# cs301_template.net
KiCad netlist of a schematic drawn in Altium Designer
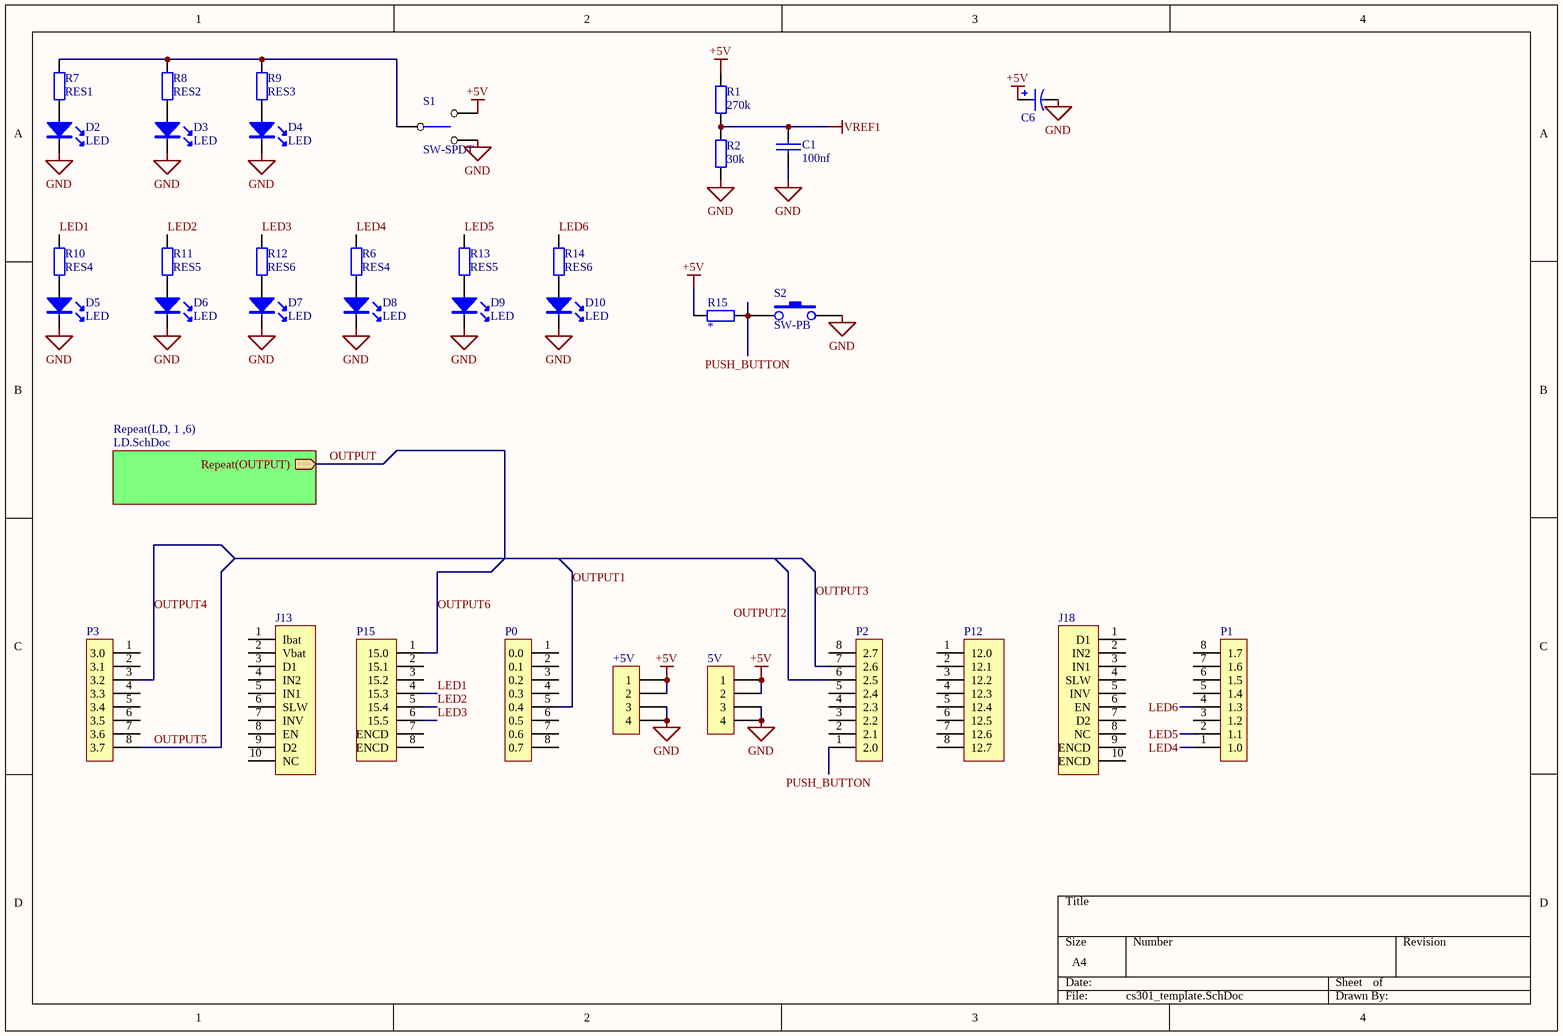
[diagram p0: cs301_template.SchDoc]

(export (version "E")
  (design (tool "Eeschema 10.0.6"))
  (components
    (comp (ref "+5V")
      (value "5V")
      (footprint "IDC4")
      (description "Connector")
      (libsource (lib "Miscellaneous Devices") (part "CON4"))
    )
    (comp (ref "5V")
      (value "5V")
      (footprint "IDC4")
      (description "Connector")
      (libsource (lib "Miscellaneous Devices") (part "CON4"))
    )
    (comp (ref "C1")
      (value "100nf")
      (footprint "0805 CAP")
      (description "SMT ceramic capacitor 0805 size")
      (libsource (lib "COMSYS301_2025") (part "CerCap_SMT_0805"))
    )
    (comp (ref "C6")
      (value "*")
      (footprint "CAP POL 8x5.4mm SMT")
      (description "CAP ALUM 22UF 20% 50V SMD (Model: UWX1H220MCL1GB)")
      (fields
        (field (name "MANUFACTURER") "Nichicon")
        (field (name "MANUFACTURER PART NUMBER") "UWX1V220MCL1GB")
      )
      (libsource (lib "COMSYS301_2025") (part "ElecCap_SMT_8D0"))
    )
    (comp (ref "D2") (value "LED") (footprint "LED0.1/5MM") (libsource (lib "COMSYS301_2025") (part "LED")))
    (comp (ref "D3") (value "LED") (footprint "LED0.1/5MM") (libsource (lib "COMSYS301_2025") (part "LED")))
    (comp (ref "D4") (value "LED") (footprint "LED0.1/5MM") (libsource (lib "COMSYS301_2025") (part "LED")))
    (comp (ref "D5") (value "LED") (footprint "LED0.1/5MM") (libsource (lib "COMSYS301_2025") (part "LED")))
    (comp (ref "D6") (value "LED") (footprint "LED0.1/5MM") (libsource (lib "COMSYS301_2025") (part "LED")))
    (comp (ref "D7") (value "LED") (footprint "LED0.1/5MM") (libsource (lib "COMSYS301_2025") (part "LED")))
    (comp (ref "D8") (value "LED") (footprint "LED0.1/5MM") (libsource (lib "COMSYS301_2025") (part "LED")))
    (comp (ref "D9") (value "LED") (footprint "LED0.1/5MM") (libsource (lib "COMSYS301_2025") (part "LED")))
    (comp (ref "D10") (value "LED") (footprint "LED0.1/5MM") (libsource (lib "COMSYS301_2025") (part "LED")))
    (comp (ref "J13")
      (value "CON10")
      (footprint "idc10")
      (description "Connector")
      (libsource (lib "Miscellaneous Devices") (part "CON10"))
    )
    (comp (ref "J18")
      (value "CON10")
      (footprint "IDC10")
      (description "Connector")
      (libsource (lib "") (part "CON10_1"))
    )
    (comp (ref "P0")
      (value "P0")
      (footprint "idc8")
      (description "Connector")
      (libsource (lib "") (part "CON8_1"))
    )
    (comp (ref "P1")
      (value "P1")
      (footprint "idc8")
      (description "Connector")
      (libsource (lib "") (part "CON8_2"))
    )
    (comp (ref "P2")
      (value "P2")
      (footprint "idc8")
      (description "Connector")
      (libsource (lib "") (part "CON8_2"))
    )
    (comp (ref "P3")
      (value "P3")
      (footprint "idc8")
      (description "Connector")
      (libsource (lib "Miscellaneous Devices") (part "CON8"))
    )
    (comp (ref "P12")
      (value "P12")
      (footprint "idc8")
      (description "Connector")
      (libsource (lib "Miscellaneous Devices") (part "CON8_1"))
    )
    (comp (ref "P15")
      (value "P15")
      (footprint "idc8")
      (description "Connector")
      (libsource (lib "") (part "CON8_1_1"))
    )
    (comp (ref "R1")
      (value "270k")
      (footprint "0805 RES")
      (description "0805 resistor")
      (fields (field (name "PUBLISHER") "Altium Limited"))
      (libsource (lib "COMSYS301_2025") (part "Res_SMT_0805"))
    )
    (comp (ref "R2")
      (value "30k")
      (footprint "0805 RES")
      (description "0805 resistor")
      (fields (field (name "PUBLISHER") "Altium Limited"))
      (libsource (lib "COMSYS301_2025") (part "Res_SMT_0805"))
    )
    (comp (ref "R6")
      (value "RES4")
      (footprint "0805 RES")
      (description "0805 resistor")
      (fields (field (name "PUBLISHER") "Altium Limited"))
      (libsource (lib "COMSYS301_2025") (part "Res_SMT_0805"))
    )
    (comp (ref "R7")
      (value "RES1")
      (footprint "0805 RES")
      (description "0805 resistor")
      (fields (field (name "PUBLISHER") "Altium Limited"))
      (libsource (lib "COMSYS301_2025") (part "Res_SMT_0805"))
    )
    (comp (ref "R8")
      (value "RES2")
      (footprint "0805 RES")
      (description "0805 resistor")
      (fields (field (name "PUBLISHER") "Altium Limited"))
      (libsource (lib "COMSYS301_2025") (part "Res_SMT_0805"))
    )
    (comp (ref "R9")
      (value "RES3")
      (footprint "0805 RES")
      (description "0805 resistor")
      (fields (field (name "PUBLISHER") "Altium Limited"))
      (libsource (lib "COMSYS301_2025") (part "Res_SMT_0805"))
    )
    (comp (ref "R10")
      (value "RES4")
      (footprint "0805 RES")
      (description "0805 resistor")
      (fields (field (name "PUBLISHER") "Altium Limited"))
      (libsource (lib "COMSYS301_2025") (part "Res_SMT_0805"))
    )
    (comp (ref "R11")
      (value "RES5")
      (footprint "0805 RES")
      (description "0805 resistor")
      (fields (field (name "PUBLISHER") "Altium Limited"))
      (libsource (lib "COMSYS301_2025") (part "Res_SMT_0805"))
    )
    (comp (ref "R12")
      (value "RES6")
      (footprint "0805 RES")
      (description "0805 resistor")
      (fields (field (name "PUBLISHER") "Altium Limited"))
      (libsource (lib "COMSYS301_2025") (part "Res_SMT_0805"))
    )
    (comp (ref "R13")
      (value "RES5")
      (footprint "0805 RES")
      (description "0805 resistor")
      (fields (field (name "PUBLISHER") "Altium Limited"))
      (libsource (lib "COMSYS301_2025") (part "Res_SMT_0805"))
    )
    (comp (ref "R14")
      (value "RES6")
      (footprint "0805 RES")
      (description "0805 resistor")
      (fields (field (name "PUBLISHER") "Altium Limited"))
      (libsource (lib "COMSYS301_2025") (part "Res_SMT_0805"))
    )
    (comp (ref "R15")
      (value "*")
      (footprint "0805 RES")
      (description "0805 resistor")
      (fields (field (name "PUBLISHER") "Altium Limited"))
      (libsource (lib "") (part "Res_SMT_0805_1"))
    )
    (comp (ref "S1")
      (value "SW-SPDT")
      (footprint "SW-SPDT")
      (description "Toggle Switch")
      (libsource (lib "COMSYS301_2025") (part "SW-SPDT"))
    )
    (comp (ref "S2")
      (value "SW-PB")
      (footprint "SW-PB")
      (description "Push Button Switch")
      (libsource (lib "COMSYS301_2025") (part "SW-PB"))
    )
  )
  (nets
    (net (code "1") (name "+5V") (class "Default")
      (node (ref "+5V") (pin "1") (pinfunction "1_1") (pintype "passive"))
      (node (ref "+5V") (pin "2") (pinfunction "2_2") (pintype "passive"))
      (node (ref "5V") (pin "1") (pinfunction "1_1") (pintype "passive"))
      (node (ref "5V") (pin "2") (pinfunction "2_2") (pintype "passive"))
      (node (ref "C6") (pin "1") (pinfunction "1_1") (pintype "passive"))
      (node (ref "R1") (pin "2") (pinfunction "2_2") (pintype "passive"))
      (node (ref "R15") (pin "1") (pinfunction "1_1") (pintype "passive"))
      (node (ref "S1") (pin "1") (pinfunction "1_1") (pintype "passive"))
    )
    (net (code "2") (name "/LED1") (class "Default")
      (node (ref "P15") (pin "4") (pinfunction "15.3_4") (pintype "passive"))
      (node (ref "R10") (pin "2") (pinfunction "2_2") (pintype "passive"))
    )
    (net (code "3") (name "/LED2") (class "Default")
      (node (ref "P15") (pin "5") (pinfunction "15.4_5") (pintype "passive"))
      (node (ref "R11") (pin "2") (pinfunction "2_2") (pintype "passive"))
    )
    (net (code "4") (name "/LED3") (class "Default")
      (node (ref "P15") (pin "6") (pinfunction "15.5_6") (pintype "passive"))
      (node (ref "R12") (pin "2") (pinfunction "2_2") (pintype "passive"))
    )
    (net (code "5") (name "/LED4") (class "Default")
      (node (ref "P1") (pin "1") (pinfunction "2.0_1") (pintype "passive"))
      (node (ref "R6") (pin "2") (pinfunction "2_2") (pintype "passive"))
    )
    (net (code "6") (name "/LED5") (class "Default")
      (node (ref "P1") (pin "2") (pinfunction "2.1_2") (pintype "passive"))
      (node (ref "R13") (pin "2") (pinfunction "2_2") (pintype "passive"))
    )
    (net (code "7") (name "/LED6") (class "Default")
      (node (ref "P1") (pin "4") (pinfunction "2.3_4") (pintype "passive"))
      (node (ref "R14") (pin "2") (pinfunction "2_2") (pintype "passive"))
    )
    (net (code "9") (name "/OUTPUT1") (class "Default")
      (node (ref "P0") (pin "5") (pinfunction "0.4_5") (pintype "passive"))
    )
    (net (code "10") (name "/OUTPUT2") (class "Default")
      (node (ref "P2") (pin "6") (pinfunction "2.5_6") (pintype "passive"))
    )
    (net (code "11") (name "/OUTPUT3") (class "Default")
      (node (ref "P2") (pin "7") (pinfunction "2.6_7") (pintype "passive"))
    )
    (net (code "12") (name "/OUTPUT4") (class "Default")
      (node (ref "P3") (pin "3") (pinfunction "3.2_3") (pintype "passive"))
    )
    (net (code "13") (name "/OUTPUT5") (class "Default")
      (node (ref "P3") (pin "8") (pinfunction "3.7_8") (pintype "passive"))
    )
    (net (code "14") (name "/OUTPUT6") (class "Default")
      (node (ref "P15") (pin "1") (pinfunction "15.0_1") (pintype "passive"))
    )
    (net (code "15") (name "/PUSH_BUTTON") (class "Default")
      (node (ref "P2") (pin "1") (pinfunction "2.0_1") (pintype "passive"))
      (node (ref "R15") (pin "2") (pinfunction "2_2") (pintype "passive"))
      (node (ref "S2") (pin "1") (pinfunction "1_1") (pintype "passive"))
    )
    (net (code "17") (name "GND") (class "Default")
      (node (ref "+5V") (pin "3") (pinfunction "3_3") (pintype "passive"))
      (node (ref "+5V") (pin "4") (pinfunction "4_4") (pintype "passive"))
      (node (ref "5V") (pin "3") (pinfunction "3_3") (pintype "passive"))
      (node (ref "5V") (pin "4") (pinfunction "4_4") (pintype "passive"))
      (node (ref "C1") (pin "2") (pinfunction "2_2") (pintype "passive"))
      (node (ref "C6") (pin "2") (pinfunction "2_2") (pintype "passive"))
      (node (ref "D10") (pin "K") (pinfunction "2_K") (pintype "passive"))
      (node (ref "D2") (pin "K") (pinfunction "2_K") (pintype "passive"))
      (node (ref "D3") (pin "K") (pinfunction "2_K") (pintype "passive"))
      (node (ref "D4") (pin "K") (pinfunction "2_K") (pintype "passive"))
      (node (ref "D5") (pin "K") (pinfunction "2_K") (pintype "passive"))
      (node (ref "D6") (pin "K") (pinfunction "2_K") (pintype "passive"))
      (node (ref "D7") (pin "K") (pinfunction "2_K") (pintype "passive"))
      (node (ref "D8") (pin "K") (pinfunction "2_K") (pintype "passive"))
      (node (ref "D9") (pin "K") (pinfunction "2_K") (pintype "passive"))
      (node (ref "R2") (pin "1") (pinfunction "1_1") (pintype "passive"))
      (node (ref "S1") (pin "3") (pinfunction "3_3") (pintype "passive"))
      (node (ref "S2") (pin "2") (pinfunction "2_2") (pintype "passive"))
    )
    (net (code "18") (name "Net-(D2-1)") (class "Default")
      (node (ref "D2") (pin "A") (pinfunction "1_A") (pintype "passive"))
      (node (ref "R7") (pin "1") (pinfunction "1_1") (pintype "passive"))
    )
    (net (code "19") (name "Net-(D3-1)") (class "Default")
      (node (ref "D3") (pin "A") (pinfunction "1_A") (pintype "passive"))
      (node (ref "R8") (pin "1") (pinfunction "1_1") (pintype "passive"))
    )
    (net (code "20") (name "Net-(D4-1)") (class "Default")
      (node (ref "D4") (pin "A") (pinfunction "1_A") (pintype "passive"))
      (node (ref "R9") (pin "1") (pinfunction "1_1") (pintype "passive"))
    )
    (net (code "21") (name "Net-(D5-1)") (class "Default")
      (node (ref "D5") (pin "A") (pinfunction "1_A") (pintype "passive"))
      (node (ref "R10") (pin "1") (pinfunction "1_1") (pintype "passive"))
    )
    (net (code "22") (name "Net-(D6-1)") (class "Default")
      (node (ref "D6") (pin "A") (pinfunction "1_A") (pintype "passive"))
      (node (ref "R11") (pin "1") (pinfunction "1_1") (pintype "passive"))
    )
    (net (code "23") (name "Net-(D7-1)") (class "Default")
      (node (ref "D7") (pin "A") (pinfunction "1_A") (pintype "passive"))
      (node (ref "R12") (pin "1") (pinfunction "1_1") (pintype "passive"))
    )
    (net (code "24") (name "Net-(D8-1)") (class "Default")
      (node (ref "D8") (pin "A") (pinfunction "1_A") (pintype "passive"))
      (node (ref "R6") (pin "1") (pinfunction "1_1") (pintype "passive"))
    )
    (net (code "25") (name "Net-(D9-1)") (class "Default")
      (node (ref "D9") (pin "A") (pinfunction "1_A") (pintype "passive"))
      (node (ref "R13") (pin "1") (pinfunction "1_1") (pintype "passive"))
    )
    (net (code "26") (name "Net-(D10-1)") (class "Default")
      (node (ref "D10") (pin "A") (pinfunction "1_A") (pintype "passive"))
      (node (ref "R14") (pin "1") (pinfunction "1_1") (pintype "passive"))
    )
    (net (code "27") (name "Net-(R7-Pad2)") (class "Default")
      (node (ref "R7") (pin "2") (pinfunction "2_2") (pintype "passive"))
      (node (ref "R8") (pin "2") (pinfunction "2_2") (pintype "passive"))
      (node (ref "R9") (pin "2") (pinfunction "2_2") (pintype "passive"))
      (node (ref "S1") (pin "2") (pinfunction "2_2") (pintype "passive"))
    )
    (net (code "28") (name "VREF1") (class "Default")
      (node (ref "C1") (pin "1") (pinfunction "1_1") (pintype "passive"))
      (node (ref "R1") (pin "1") (pinfunction "1_1") (pintype "passive"))
      (node (ref "R2") (pin "2") (pinfunction "2_2") (pintype "passive"))
    )
    (net (code "29") (name "unconnected-(J13-D1-Pad3)") (class "Default")
      (node (ref "J13") (pin "3") (pinfunction "D1_3") (pintype "passive"))
    )
    (net (code "30") (name "unconnected-(J13-D2-Pad9)") (class "Default")
      (node (ref "J13") (pin "9") (pinfunction "D2_9") (pintype "passive"))
    )
    (net (code "31") (name "unconnected-(J13-EN-Pad8)") (class "Default")
      (node (ref "J13") (pin "8") (pinfunction "EN_8") (pintype "passive"))
    )
    (net (code "32") (name "unconnected-(J13-IN1-Pad5)") (class "Default")
      (node (ref "J13") (pin "5") (pinfunction "IN1_5") (pintype "passive"))
    )
    (net (code "33") (name "unconnected-(J13-IN2-Pad4)") (class "Default")
      (node (ref "J13") (pin "4") (pinfunction "IN2_4") (pintype "passive"))
    )
    (net (code "34") (name "unconnected-(J13-INV-Pad7)") (class "Default")
      (node (ref "J13") (pin "7") (pinfunction "INV_7") (pintype "passive"))
    )
    (net (code "35") (name "unconnected-(J13-Ibat-Pad1)") (class "Default")
      (node (ref "J13") (pin "1") (pinfunction "Ibat_1") (pintype "passive"))
    )
    (net (code "36") (name "unconnected-(J13-NC-Pad10)") (class "Default")
      (node (ref "J13") (pin "10") (pinfunction "NC_10") (pintype "passive"))
    )
    (net (code "37") (name "unconnected-(J13-SLW-Pad6)") (class "Default")
      (node (ref "J13") (pin "6") (pinfunction "SLW_6") (pintype "passive"))
    )
    (net (code "38") (name "unconnected-(J13-Vbat-Pad2)") (class "Default")
      (node (ref "J13") (pin "2") (pinfunction "Vbat_2") (pintype "passive"))
    )
    (net (code "39") (name "unconnected-(J18-D1-Pad1)") (class "Default")
      (node (ref "J18") (pin "1") (pinfunction "D1_1") (pintype "passive"))
    )
    (net (code "40") (name "unconnected-(J18-D2-Pad7)") (class "Default")
      (node (ref "J18") (pin "7") (pinfunction "D2_7") (pintype "passive"))
    )
    (net (code "41") (name "unconnected-(J18-EN-Pad6)") (class "Default")
      (node (ref "J18") (pin "6") (pinfunction "EN_6") (pintype "passive"))
    )
    (net (code "42") (name "unconnected-(J18-ENCD-Pad9)") (class "Default")
      (node (ref "J18") (pin "9") (pinfunction "ENCD_9") (pintype "passive"))
    )
    (net (code "43") (name "unconnected-(J18-ENCD-Pad10)") (class "Default")
      (node (ref "J18") (pin "10") (pinfunction "ENCD_10") (pintype "passive"))
    )
    (net (code "44") (name "unconnected-(J18-IN1-Pad3)") (class "Default")
      (node (ref "J18") (pin "3") (pinfunction "IN1_3") (pintype "passive"))
    )
    (net (code "45") (name "unconnected-(J18-IN2-Pad2)") (class "Default")
      (node (ref "J18") (pin "2") (pinfunction "IN2_2") (pintype "passive"))
    )
    (net (code "46") (name "unconnected-(J18-INV-Pad5)") (class "Default")
      (node (ref "J18") (pin "5") (pinfunction "INV_5") (pintype "passive"))
    )
    (net (code "47") (name "unconnected-(J18-NC-Pad8)") (class "Default")
      (node (ref "J18") (pin "8") (pinfunction "NC_8") (pintype "passive"))
    )
    (net (code "48") (name "unconnected-(J18-SLW-Pad4)") (class "Default")
      (node (ref "J18") (pin "4") (pinfunction "SLW_4") (pintype "passive"))
    )
    (net (code "49") (name "unconnected-(P0-0.0-Pad1)") (class "Default")
      (node (ref "P0") (pin "1") (pinfunction "0.0_1") (pintype "passive"))
    )
    (net (code "50") (name "unconnected-(P0-0.1-Pad2)") (class "Default")
      (node (ref "P0") (pin "2") (pinfunction "0.1_2") (pintype "passive"))
    )
    (net (code "51") (name "unconnected-(P0-0.2-Pad3)") (class "Default")
      (node (ref "P0") (pin "3") (pinfunction "0.2_3") (pintype "passive"))
    )
    (net (code "52") (name "unconnected-(P0-0.3-Pad4)") (class "Default")
      (node (ref "P0") (pin "4") (pinfunction "0.3_4") (pintype "passive"))
    )
    (net (code "53") (name "unconnected-(P0-0.5-Pad6)") (class "Default")
      (node (ref "P0") (pin "6") (pinfunction "0.5_6") (pintype "passive"))
    )
    (net (code "54") (name "unconnected-(P0-0.6-Pad7)") (class "Default")
      (node (ref "P0") (pin "7") (pinfunction "0.6_7") (pintype "passive"))
    )
    (net (code "55") (name "unconnected-(P0-0.7-Pad8)") (class "Default")
      (node (ref "P0") (pin "8") (pinfunction "0.7_8") (pintype "passive"))
    )
    (net (code "56") (name "unconnected-(P1-2.2-Pad3)") (class "Default")
      (node (ref "P1") (pin "3") (pinfunction "2.2_3") (pintype "passive"))
    )
    (net (code "57") (name "unconnected-(P1-2.4-Pad5)") (class "Default")
      (node (ref "P1") (pin "5") (pinfunction "2.4_5") (pintype "passive"))
    )
    (net (code "58") (name "unconnected-(P1-2.5-Pad6)") (class "Default")
      (node (ref "P1") (pin "6") (pinfunction "2.5_6") (pintype "passive"))
    )
    (net (code "59") (name "unconnected-(P1-2.6-Pad7)") (class "Default")
      (node (ref "P1") (pin "7") (pinfunction "2.6_7") (pintype "passive"))
    )
    (net (code "60") (name "unconnected-(P1-2.7-Pad8)") (class "Default")
      (node (ref "P1") (pin "8") (pinfunction "2.7_8") (pintype "passive"))
    )
    (net (code "61") (name "unconnected-(P2-2.1-Pad2)") (class "Default")
      (node (ref "P2") (pin "2") (pinfunction "2.1_2") (pintype "passive"))
    )
    (net (code "62") (name "unconnected-(P2-2.2-Pad3)") (class "Default")
      (node (ref "P2") (pin "3") (pinfunction "2.2_3") (pintype "passive"))
    )
    (net (code "63") (name "unconnected-(P2-2.3-Pad4)") (class "Default")
      (node (ref "P2") (pin "4") (pinfunction "2.3_4") (pintype "passive"))
    )
    (net (code "64") (name "unconnected-(P2-2.4-Pad5)") (class "Default")
      (node (ref "P2") (pin "5") (pinfunction "2.4_5") (pintype "passive"))
    )
    (net (code "65") (name "unconnected-(P2-2.7-Pad8)") (class "Default")
      (node (ref "P2") (pin "8") (pinfunction "2.7_8") (pintype "passive"))
    )
    (net (code "66") (name "unconnected-(P3-3.0-Pad1)") (class "Default")
      (node (ref "P3") (pin "1") (pinfunction "3.0_1") (pintype "passive"))
    )
    (net (code "67") (name "unconnected-(P3-3.1-Pad2)") (class "Default")
      (node (ref "P3") (pin "2") (pinfunction "3.1_2") (pintype "passive"))
    )
    (net (code "68") (name "unconnected-(P3-3.3-Pad4)") (class "Default")
      (node (ref "P3") (pin "4") (pinfunction "3.3_4") (pintype "passive"))
    )
    (net (code "69") (name "unconnected-(P3-3.4-Pad5)") (class "Default")
      (node (ref "P3") (pin "5") (pinfunction "3.4_5") (pintype "passive"))
    )
    (net (code "70") (name "unconnected-(P3-3.5-Pad6)") (class "Default")
      (node (ref "P3") (pin "6") (pinfunction "3.5_6") (pintype "passive"))
    )
    (net (code "71") (name "unconnected-(P3-3.6-Pad7)") (class "Default")
      (node (ref "P3") (pin "7") (pinfunction "3.6_7") (pintype "passive"))
    )
    (net (code "72") (name "unconnected-(P12-12.0-Pad1)") (class "Default")
      (node (ref "P12") (pin "1") (pinfunction "12.0_1") (pintype "passive"))
    )
    (net (code "73") (name "unconnected-(P12-12.1-Pad2)") (class "Default")
      (node (ref "P12") (pin "2") (pinfunction "12.1_2") (pintype "passive"))
    )
    (net (code "74") (name "unconnected-(P12-12.2-Pad3)") (class "Default")
      (node (ref "P12") (pin "3") (pinfunction "12.2_3") (pintype "passive"))
    )
    (net (code "75") (name "unconnected-(P12-12.3-Pad4)") (class "Default")
      (node (ref "P12") (pin "4") (pinfunction "12.3_4") (pintype "passive"))
    )
    (net (code "76") (name "unconnected-(P12-12.4-Pad5)") (class "Default")
      (node (ref "P12") (pin "5") (pinfunction "12.4_5") (pintype "passive"))
    )
    (net (code "77") (name "unconnected-(P12-12.5-Pad6)") (class "Default")
      (node (ref "P12") (pin "6") (pinfunction "12.5_6") (pintype "passive"))
    )
    (net (code "78") (name "unconnected-(P12-12.6-Pad7)") (class "Default")
      (node (ref "P12") (pin "7") (pinfunction "12.6_7") (pintype "passive"))
    )
    (net (code "79") (name "unconnected-(P12-12.7-Pad8)") (class "Default")
      (node (ref "P12") (pin "8") (pinfunction "12.7_8") (pintype "passive"))
    )
    (net (code "80") (name "unconnected-(P15-15.1-Pad2)") (class "Default")
      (node (ref "P15") (pin "2") (pinfunction "15.1_2") (pintype "passive"))
    )
    (net (code "81") (name "unconnected-(P15-15.2-Pad3)") (class "Default")
      (node (ref "P15") (pin "3") (pinfunction "15.2_3") (pintype "passive"))
    )
    (net (code "82") (name "unconnected-(P15-ENCD-Pad7)") (class "Default")
      (node (ref "P15") (pin "7") (pinfunction "ENCD_7") (pintype "passive"))
    )
    (net (code "83") (name "unconnected-(P15-ENCD-Pad8)") (class "Default")
      (node (ref "P15") (pin "8") (pinfunction "ENCD_8") (pintype "passive"))
    )
  )
)
